# Quadcopter.net
KiCad netlist of a schematic drawn in Altium Designer
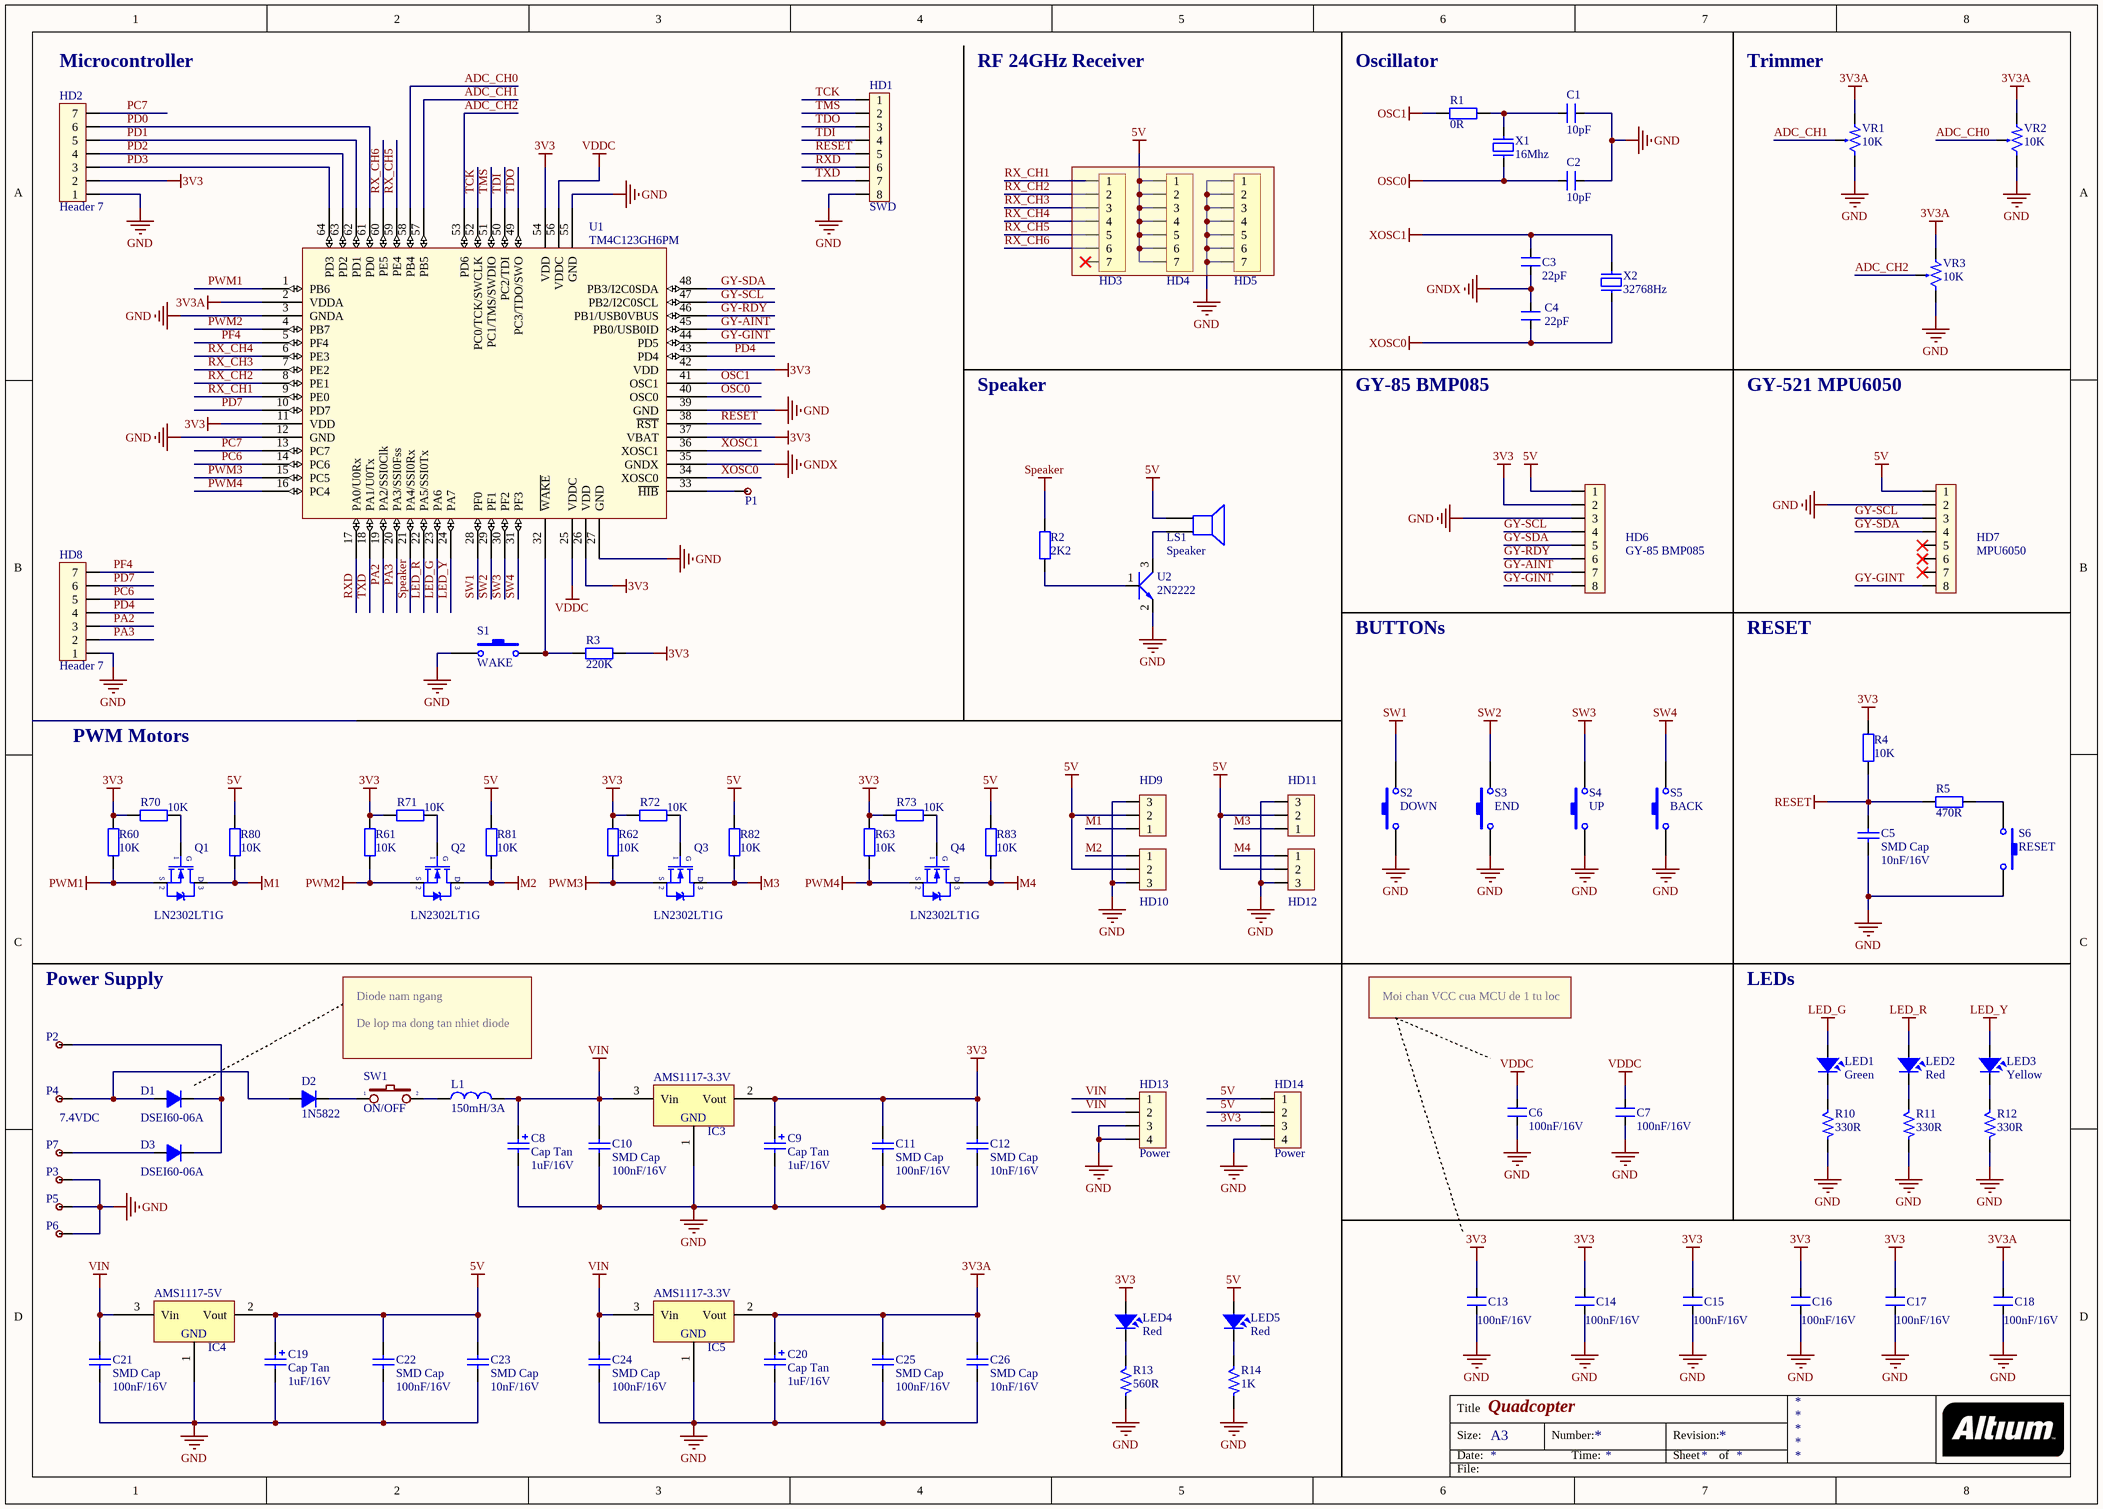
[diagram p0: Quadcopter.SchDoc]

(export (version "E")
  (design (tool "Eeschema 10.0.6"))
  (components
    (comp (ref "C1")
      (value "10pF")
      (footprint "C0603")
      (description "0805-SMD Capacitor")
      (libsource (lib "syhaunguyen") (part "CN1"))
    )
    (comp (ref "C2")
      (value "10pF")
      (footprint "C0603")
      (description "0805-SMD Capacitor")
      (libsource (lib "syhaunguyen") (part "CN1"))
    )
    (comp (ref "C3")
      (value "22pF")
      (footprint "C0603")
      (description "0805-SMD Capacitor")
      (libsource (lib "syhaunguyen") (part "CN1"))
    )
    (comp (ref "C4")
      (value "22pF")
      (footprint "C0603")
      (description "0805-SMD Capacitor")
      (libsource (lib "syhaunguyen") (part "CN1"))
    )
    (comp (ref "C5")
      (value "SMD Cap")
      (footprint "C0603")
      (description "0805-10nF-50V Cap")
      (fields (field (name "ALTIUM_VALUE") "10nF/16V"))
      (libsource (lib "Miscellaneous Devices") (part "Cap"))
    )
    (comp (ref "C6")
      (value "100nF/16V")
      (footprint "C0603")
      (description "0805-SMD Capacitor")
      (fields (field (name "Comment") "SMD Cap"))
      (libsource (lib "syhaunguyen") (part "CN1"))
    )
    (comp (ref "C7")
      (value "100nF/16V")
      (footprint "C0603")
      (description "0805-SMD Capacitor")
      (fields (field (name "Comment") "SMD Cap"))
      (libsource (lib "syhaunguyen") (part "CN1"))
    )
    (comp (ref "C8")
      (value "Cap Tan")
      (footprint "CAP_TANTA_1uF_16V")
      (description "Cap Tantalum")
      (fields (field (name "ALTIUM_VALUE") "1uF/16V"))
      (libsource (lib "PassiveComponents_Sau") (part "Cap Pol2"))
    )
    (comp (ref "C9")
      (value "Cap Tan")
      (footprint "CAP_TANTA_1uF_16V")
      (description "Cap Tantalum")
      (fields (field (name "ALTIUM_VALUE") "1uF/16V"))
      (libsource (lib "PassiveComponents_Sau") (part "Cap Pol2"))
    )
    (comp (ref "C10")
      (value "SMD Cap")
      (footprint "C0603")
      (description "SMD Capacitor")
      (fields (field (name "ALTIUM_VALUE") "100nF/16V"))
      (libsource (lib "PassiveComponents_Sau") (part "Cap Cera"))
    )
    (comp (ref "C11")
      (value "SMD Cap")
      (footprint "C0603")
      (description "SMD Capacitor")
      (fields (field (name "ALTIUM_VALUE") "100nF/16V"))
      (libsource (lib "PassiveComponents_Sau") (part "Cap Cera"))
    )
    (comp (ref "C12")
      (value "SMD Cap")
      (footprint "C0603")
      (description "SMD Capacitor")
      (fields (field (name "ALTIUM_VALUE") "10nF/16V"))
      (libsource (lib "PassiveComponents_Sau") (part "Cap Cera"))
    )
    (comp (ref "C13")
      (value "100nF/16V")
      (footprint "C0603")
      (description "0805-SMD Capacitor")
      (fields (field (name "Comment") "SMD Cap"))
      (libsource (lib "syhaunguyen") (part "CN1"))
    )
    (comp (ref "C14")
      (value "100nF/16V")
      (footprint "C0603")
      (description "0805-SMD Capacitor")
      (fields (field (name "Comment") "SMD Cap"))
      (libsource (lib "syhaunguyen") (part "CN1"))
    )
    (comp (ref "C15")
      (value "100nF/16V")
      (footprint "C0603")
      (description "0805-SMD Capacitor")
      (fields (field (name "Comment") "SMD Cap"))
      (libsource (lib "syhaunguyen") (part "CN1"))
    )
    (comp (ref "C16")
      (value "100nF/16V")
      (footprint "C0603")
      (description "0805-SMD Capacitor")
      (fields (field (name "Comment") "SMD Cap"))
      (libsource (lib "syhaunguyen") (part "CN1"))
    )
    (comp (ref "C17")
      (value "100nF/16V")
      (footprint "C0603")
      (description "0805-SMD Capacitor")
      (fields (field (name "Comment") "SMD Cap"))
      (libsource (lib "syhaunguyen") (part "CN1"))
    )
    (comp (ref "C18")
      (value "100nF/16V")
      (footprint "C0603")
      (description "0805-SMD Capacitor")
      (fields (field (name "Comment") "SMD Cap"))
      (libsource (lib "syhaunguyen") (part "CN1"))
    )
    (comp (ref "C19")
      (value "Cap Tan")
      (footprint "CAP_TANTA_1uF_16V")
      (description "Cap Tantalum")
      (fields (field (name "ALTIUM_VALUE") "1uF/16V"))
      (libsource (lib "PassiveComponents_Sau") (part "Cap Pol2"))
    )
    (comp (ref "C20")
      (value "Cap Tan")
      (footprint "CAP_TANTA_1uF_16V")
      (description "Cap Tantalum")
      (fields (field (name "ALTIUM_VALUE") "1uF/16V"))
      (libsource (lib "PassiveComponents_Sau") (part "Cap Pol2"))
    )
    (comp (ref "C21")
      (value "SMD Cap")
      (footprint "C0603")
      (description "SMD Capacitor")
      (fields (field (name "ALTIUM_VALUE") "100nF/16V"))
      (libsource (lib "PassiveComponents_Sau") (part "Cap Cera"))
    )
    (comp (ref "C22")
      (value "SMD Cap")
      (footprint "C0603")
      (description "SMD Capacitor")
      (fields (field (name "ALTIUM_VALUE") "100nF/16V"))
      (libsource (lib "PassiveComponents_Sau") (part "Cap Cera"))
    )
    (comp (ref "C23")
      (value "SMD Cap")
      (footprint "C0603")
      (description "SMD Capacitor")
      (fields (field (name "ALTIUM_VALUE") "10nF/16V"))
      (libsource (lib "PassiveComponents_Sau") (part "Cap Cera"))
    )
    (comp (ref "C24")
      (value "SMD Cap")
      (footprint "C0603")
      (description "SMD Capacitor")
      (fields (field (name "ALTIUM_VALUE") "100nF/16V"))
      (libsource (lib "PassiveComponents_Sau") (part "Cap Cera"))
    )
    (comp (ref "C25")
      (value "SMD Cap")
      (footprint "C0603")
      (description "SMD Capacitor")
      (fields (field (name "ALTIUM_VALUE") "100nF/16V"))
      (libsource (lib "PassiveComponents_Sau") (part "Cap Cera"))
    )
    (comp (ref "C26")
      (value "SMD Cap")
      (footprint "C0603")
      (description "SMD Capacitor")
      (fields (field (name "ALTIUM_VALUE") "10nF/16V"))
      (libsource (lib "PassiveComponents_Sau") (part "Cap Cera"))
    )
    (comp (ref "D1")
      (value "DSEI60-06A")
      (footprint "DSEI60-06A")
      (description "Diode 60A")
      (libsource (lib "VNELEK") (part "D1A"))
    )
    (comp (ref "D2")
      (value "1N5822")
      (footprint "1N5822")
      (description "Diode  3A")
      (libsource (lib "VNELEK") (part "D1A"))
    )
    (comp (ref "D3")
      (value "DSEI60-06A")
      (footprint "DSEI60-06A")
      (description "Diode 60A")
      (libsource (lib "VNELEK") (part "D1A"))
    )
    (comp (ref "HD1")
      (value "SWD")
      (footprint "Header_8")
      (description "Hedear 8")
      (fields (field (name "CREAT BY") "VanDungEvn@Gmail.com"))
      (libsource (lib "VNELEK") (part "Hed8"))
    )
    (comp (ref "HD2") (value "Header 7") (footprint "Header_7") (libsource (lib "") (part "Hed7_1")))
    (comp (ref "HD3") (value "Header 7") (footprint "Header_7") (libsource (lib "Tran Tuan") (part "Hed7")))
    (comp (ref "HD4") (value "Header 7") (footprint "Header_7") (libsource (lib "Tran Tuan") (part "Hed7")))
    (comp (ref "HD5") (value "Header 7") (footprint "Header_7") (libsource (lib "Tran Tuan") (part "Hed7")))
    (comp (ref "HD6")
      (value "GY-85 BMP085")
      (footprint "Header_8")
      (description "Hedear 8")
      (fields (field (name "CREAT BY") "VanDungEvn@Gmail.com"))
      (libsource (lib "VNELEK") (part "Hed8"))
    )
    (comp (ref "HD7")
      (value "MPU6050")
      (footprint "Header_8")
      (description "Hedear 8")
      (fields (field (name "CREAT BY") "VanDungEvn@Gmail.com"))
      (libsource (lib "VNELEK") (part "Hed8"))
    )
    (comp (ref "HD8") (value "Header 7") (footprint "Header_7") (libsource (lib "") (part "Hed7_1")))
    (comp (ref "HD9")
      (value "Header 3")
      (footprint "JP3H")
      (description "Header 3 (Green)")
      (libsource (lib "") (part "Hed3_1"))
    )
    (comp (ref "HD10")
      (value "Header 3")
      (footprint "JP3H")
      (description "Header 3 (Green)")
      (libsource (lib "VNELEK") (part "Hed3"))
    )
    (comp (ref "HD11")
      (value "Header 3")
      (footprint "JP3H")
      (description "Header 3 (Green)")
      (libsource (lib "") (part "Hed3_1"))
    )
    (comp (ref "HD12")
      (value "Header 3")
      (footprint "JP3H")
      (description "Header 3 (Green)")
      (libsource (lib "VNELEK") (part "Hed3"))
    )
    (comp (ref "HD13")
      (value "Power")
      (footprint "Header_4")
      (description "Header 4 (Green)")
      (libsource (lib "VNELEK") (part "Hed4"))
    )
    (comp (ref "HD14")
      (value "Power")
      (footprint "Header_4")
      (description "Header 4 (Green)")
      (libsource (lib "VNELEK") (part "Hed4"))
    )
    (comp (ref "IC3")
      (value "AMS1117-3.3V")
      (footprint "AMS1117-3.3V")
      (libsource (lib "LuanVanPIR") (part "AMS1117"))
    )
    (comp (ref "IC4")
      (value "AMS1117-5V")
      (footprint "AMS1117-3.3V")
      (libsource (lib "LuanVanPIR") (part "AMS1117"))
    )
    (comp (ref "IC5")
      (value "AMS1117-3.3V")
      (footprint "AMS1117-3.3V")
      (libsource (lib "LuanVanPIR") (part "AMS1117"))
    )
    (comp (ref "L1")
      (value "150mH/3A")
      (footprint "Inductor 150mH,3A")
      (description "Inductor")
      (libsource (lib "VNELEK") (part "L1"))
    )
    (comp (ref "LED1")
      (value "Green")
      (footprint "Led 0805G")
      (description "LED Single colour Green and Red")
      (libsource (lib "VNELEK") (part "LED"))
    )
    (comp (ref "LED2")
      (value "Red")
      (footprint "Led 0805R")
      (description "LED Single colour Green and Red")
      (libsource (lib "VNELEK") (part "LED"))
    )
    (comp (ref "LED3")
      (value "Yellow")
      (footprint "Led 0805Y")
      (description "LED Single colour Green and Red")
      (libsource (lib "VNELEK") (part "LED"))
    )
    (comp (ref "LED4")
      (value "Red")
      (footprint "Led 0805R")
      (description "LED Single colour Green and Red")
      (libsource (lib "VNELEK") (part "LED"))
    )
    (comp (ref "LED5")
      (value "Red")
      (footprint "Led 0805R")
      (description "LED Single colour Green and Red")
      (libsource (lib "VNELEK") (part "LED"))
    )
    (comp (ref "LS1")
      (value "Speaker")
      (footprint "SPEAKER")
      (description "Loudspeaker")
      (fields (field (name "PUBLISHER") "Altium Limited"))
      (libsource (lib "Miscellaneous Devices") (part "Speaker"))
    )
    (comp (ref "P1") (value "Pad") (footprint "TP1") (libsource (lib "Tran Tuan") (part "Pad")))
    (comp (ref "P2") (value "Pad") (footprint "TP1") (libsource (lib "Tran Tuan") (part "Pad")))
    (comp (ref "P3") (value "Pad") (footprint "TP1") (libsource (lib "Tran Tuan") (part "Pad")))
    (comp (ref "P4") (value "Pad") (footprint "TP1") (libsource (lib "Tran Tuan") (part "Pad")))
    (comp (ref "P5") (value "Pad") (footprint "TP1") (libsource (lib "Tran Tuan") (part "Pad")))
    (comp (ref "P6") (value "Pad") (footprint "TP1") (libsource (lib "Tran Tuan") (part "Pad")))
    (comp (ref "P7") (value "Pad") (footprint "TP1") (libsource (lib "Tran Tuan") (part "Pad")))
    (comp (ref "Q1")
      (value "LN2302LT1G")
      (description "20V N-Channel Enhancement-Mode MOSFET")
      (libsource (lib "Tran Tuan") (part "LN2302LT1G"))
    )
    (comp (ref "Q2")
      (value "LN2302LT1G")
      (description "20V N-Channel Enhancement-Mode MOSFET")
      (libsource (lib "Tran Tuan") (part "LN2302LT1G"))
    )
    (comp (ref "Q3")
      (value "LN2302LT1G")
      (description "20V N-Channel Enhancement-Mode MOSFET")
      (libsource (lib "Tran Tuan") (part "LN2302LT1G"))
    )
    (comp (ref "Q4")
      (value "LN2302LT1G")
      (description "20V N-Channel Enhancement-Mode MOSFET")
      (libsource (lib "Tran Tuan") (part "LN2302LT1G"))
    )
    (comp (ref "R1")
      (value "0R")
      (footprint "RESC2012L")
      (description "Resistor")
      (fields (field (name "Comment") "Res2") (field (name "PUBLISHER") "Altium Limited"))
      (libsource (lib "") (part "Res2_2"))
    )
    (comp (ref "R2")
      (value "2K2")
      (footprint "RESC2012L")
      (description "Resistor")
      (fields (field (name "Comment") "Res2") (field (name "PUBLISHER") "Altium Limited"))
      (libsource (lib "Miscellaneous Devices") (part "Res2"))
    )
    (comp (ref "R3")
      (value "220K")
      (footprint "RESC2012L")
      (description "Resistor")
      (fields (field (name "Comment") "Res2") (field (name "PUBLISHER") "Altium Limited"))
      (libsource (lib "") (part "Res2_1"))
    )
    (comp (ref "R4")
      (value "10K")
      (footprint "RESC2012L")
      (description "Resistor")
      (fields (field (name "Comment") "Res2") (field (name "PUBLISHER") "Altium Limited"))
      (libsource (lib "") (part "Res2_3"))
    )
    (comp (ref "R5")
      (value "470R")
      (footprint "RESC2012L")
      (description "Resistor")
      (fields (field (name "Comment") "Res2") (field (name "PUBLISHER") "Altium Limited"))
      (libsource (lib "") (part "Res2_1"))
    )
    (comp (ref "R10")
      (value "330R")
      (footprint "RESC2012L")
      (description "Resistor 1/4W")
      (libsource (lib "VNELEK") (part "R"))
    )
    (comp (ref "R11")
      (value "330R")
      (footprint "RESC2012L")
      (description "Resistor 1/4W")
      (libsource (lib "VNELEK") (part "R"))
    )
    (comp (ref "R12")
      (value "330R")
      (footprint "RESC2012L")
      (description "Resistor 1/4W")
      (libsource (lib "VNELEK") (part "R"))
    )
    (comp (ref "R13")
      (value "560R")
      (footprint "RESC2012L")
      (description "Resistor 1/4W")
      (libsource (lib "VNELEK") (part "R"))
    )
    (comp (ref "R14")
      (value "1K")
      (footprint "RESC2012L")
      (description "Resistor 1/4W")
      (libsource (lib "VNELEK") (part "R"))
    )
    (comp (ref "R60")
      (value "10K")
      (footprint "RESC2012L")
      (description "Resistor")
      (fields (field (name "Comment") "Res2") (field (name "PUBLISHER") "Altium Limited"))
      (libsource (lib "") (part "Res2_3"))
    )
    (comp (ref "R61")
      (value "10K")
      (footprint "RESC2012L")
      (description "Resistor")
      (fields (field (name "Comment") "Res2") (field (name "PUBLISHER") "Altium Limited"))
      (libsource (lib "") (part "Res2_3"))
    )
    (comp (ref "R62")
      (value "10K")
      (footprint "RESC2012L")
      (description "Resistor")
      (fields (field (name "Comment") "Res2") (field (name "PUBLISHER") "Altium Limited"))
      (libsource (lib "") (part "Res2_3"))
    )
    (comp (ref "R63")
      (value "10K")
      (footprint "RESC2012L")
      (description "Resistor")
      (fields (field (name "Comment") "Res2") (field (name "PUBLISHER") "Altium Limited"))
      (libsource (lib "") (part "Res2_3"))
    )
    (comp (ref "R70")
      (value "10K")
      (footprint "RESC2012L")
      (description "Resistor")
      (fields (field (name "Comment") "Res2") (field (name "PUBLISHER") "Altium Limited"))
      (libsource (lib "") (part "Res2_1"))
    )
    (comp (ref "R71")
      (value "10K")
      (footprint "RESC2012L")
      (description "Resistor")
      (fields (field (name "Comment") "Res2") (field (name "PUBLISHER") "Altium Limited"))
      (libsource (lib "") (part "Res2_1"))
    )
    (comp (ref "R72")
      (value "10K")
      (footprint "RESC2012L")
      (description "Resistor")
      (fields (field (name "Comment") "Res2") (field (name "PUBLISHER") "Altium Limited"))
      (libsource (lib "") (part "Res2_1"))
    )
    (comp (ref "R73")
      (value "10K")
      (footprint "RESC2012L")
      (description "Resistor")
      (fields (field (name "Comment") "Res2") (field (name "PUBLISHER") "Altium Limited"))
      (libsource (lib "") (part "Res2_1"))
    )
    (comp (ref "R80")
      (value "10K")
      (footprint "RESC2012L")
      (description "Resistor")
      (fields (field (name "Comment") "Res2") (field (name "PUBLISHER") "Altium Limited"))
      (libsource (lib "") (part "Res2_3"))
    )
    (comp (ref "R81")
      (value "10K")
      (footprint "RESC2012L")
      (description "Resistor")
      (fields (field (name "Comment") "Res2") (field (name "PUBLISHER") "Altium Limited"))
      (libsource (lib "") (part "Res2_3"))
    )
    (comp (ref "R82")
      (value "10K")
      (footprint "RESC2012L")
      (description "Resistor")
      (fields (field (name "Comment") "Res2") (field (name "PUBLISHER") "Altium Limited"))
      (libsource (lib "") (part "Res2_3"))
    )
    (comp (ref "R83")
      (value "10K")
      (footprint "RESC2012L")
      (description "Resistor")
      (fields (field (name "Comment") "Res2") (field (name "PUBLISHER") "Altium Limited"))
      (libsource (lib "") (part "Res2_3"))
    )
    (comp (ref "S1")
      (value "WAKE")
      (footprint "BUTTON 2PIN TRON")
      (description "Switch")
      (fields (field (name "PUBLISHER") "Altium Limited"))
      (libsource (lib "Miscellaneous Devices") (part "SW-PB"))
    )
    (comp (ref "S2")
      (value "DOWN")
      (footprint "BUTTON 2PIN TRON")
      (description "Switch")
      (fields (field (name "PUBLISHER") "Altium Limited"))
      (libsource (lib "Miscellaneous Devices") (part "SW-PB"))
    )
    (comp (ref "S3")
      (value "END")
      (footprint "BUTTON 2PIN TRON")
      (description "Switch")
      (fields (field (name "PUBLISHER") "Altium Limited"))
      (libsource (lib "Miscellaneous Devices") (part "SW-PB"))
    )
    (comp (ref "S4")
      (value "UP")
      (footprint "BUTTON 2PIN TRON")
      (description "Switch")
      (fields (field (name "PUBLISHER") "Altium Limited"))
      (libsource (lib "Miscellaneous Devices") (part "SW-PB"))
    )
    (comp (ref "S5")
      (value "BACK")
      (footprint "BUTTON 2PIN TRON")
      (description "Switch")
      (fields (field (name "PUBLISHER") "Altium Limited"))
      (libsource (lib "Miscellaneous Devices") (part "SW-PB"))
    )
    (comp (ref "S6")
      (value "RESET")
      (footprint "BUTTON 2PIN TRON")
      (description "Switch")
      (fields (field (name "PUBLISHER") "Altium Limited"))
      (libsource (lib "Miscellaneous Devices") (part "SW-PB"))
    )
    (comp (ref "SW1")
      (value "ON/OFF")
      (footprint "CKCD11-101")
      (description "Switch button 2 pin")
      (libsource (lib "VNELEK") (part "SW2"))
    )
    (comp (ref "U1")
      (value "TM4C123GH6PM")
      (footprint "TM4C123GH6PM")
      (description "Tiva C Series Microcontroller")
      (libsource (lib "Tran Tuan") (part "TM4C123GH6PM"))
    )
    (comp (ref "U2")
      (value "2N2222")
      (footprint "MMBT2222A")
      (description "NPN switching transistors")
      (libsource (lib "Tran Tuan") (part "2N2222"))
    )
    (comp (ref "VR1")
      (value "10K")
      (footprint "VR")
      (description "Var Resistor")
      (libsource (lib "VNELEK") (part "VR1"))
    )
    (comp (ref "VR2")
      (value "10K")
      (footprint "VR")
      (description "Var Resistor")
      (libsource (lib "VNELEK") (part "VR1"))
    )
    (comp (ref "VR3")
      (value "10K")
      (footprint "VR")
      (description "Var Resistor")
      (libsource (lib "VNELEK") (part "VR1"))
    )
    (comp (ref "X1")
      (value "16Mhz")
      (footprint "CSTCE16M0V53-R0")
      (description "Crystal For all Crystal 2pin.")
      (libsource (lib "syhaunguyen") (part "XT2"))
    )
    (comp (ref "X2")
      (value "32768Hz")
      (footprint "32.678 Khz")
      (description "Crystal For all Crystal 2pin.")
      (libsource (lib "syhaunguyen") (part "XT2"))
    )
  )
  (nets
    (net (code "1") (name "/ADC_CH0") (class "Default")
      (node (ref "U1") (pin "58") (pinfunction "PB4_58") (pintype "bidirectional"))
      (node (ref "VR2") (pin "2") (pinfunction "2_2") (pintype "passive"))
    )
    (net (code "2") (name "/ADC_CH1") (class "Default")
      (node (ref "U1") (pin "57") (pinfunction "PB5_57") (pintype "bidirectional"))
      (node (ref "VR1") (pin "2") (pinfunction "2_2") (pintype "passive"))
    )
    (net (code "3") (name "/ADC_CH2") (class "Default")
      (node (ref "U1") (pin "53") (pinfunction "PD6_53") (pintype "bidirectional"))
      (node (ref "VR3") (pin "2") (pinfunction "2_2") (pintype "passive"))
    )
    (net (code "4") (name "/GY-AINT") (class "Default")
      (node (ref "HD6") (pin "7") (pinfunction "7_7") (pintype "passive"))
      (node (ref "U1") (pin "45") (pinfunction "PB0/USB0ID_45") (pintype "bidirectional"))
    )
    (net (code "5") (name "/GY-GINT") (class "Default")
      (node (ref "HD6") (pin "8") (pinfunction "8_8") (pintype "passive"))
      (node (ref "HD7") (pin "8") (pinfunction "8_8") (pintype "passive"))
      (node (ref "U1") (pin "44") (pinfunction "PD5_44") (pintype "bidirectional"))
    )
    (net (code "6") (name "/GY-RDY") (class "Default")
      (node (ref "HD6") (pin "6") (pinfunction "6_6") (pintype "passive"))
      (node (ref "U1") (pin "46") (pinfunction "PB1/USB0VBUS_46") (pintype "bidirectional"))
    )
    (net (code "7") (name "/GY-SCL") (class "Default")
      (node (ref "HD6") (pin "4") (pinfunction "4_4") (pintype "passive"))
      (node (ref "HD7") (pin "3") (pinfunction "3_3") (pintype "passive"))
      (node (ref "U1") (pin "47") (pinfunction "PB2/I2C0SCL_47") (pintype "bidirectional"))
    )
    (net (code "8") (name "/GY-SDA") (class "Default")
      (node (ref "HD6") (pin "5") (pinfunction "5_5") (pintype "passive"))
      (node (ref "HD7") (pin "4") (pinfunction "4_4") (pintype "passive"))
      (node (ref "U1") (pin "48") (pinfunction "PB3/I2C0SDA_48") (pintype "bidirectional"))
    )
    (net (code "9") (name "/PA2") (class "Default")
      (node (ref "HD8") (pin "3") (pinfunction "3_3") (pintype "passive"))
      (node (ref "U1") (pin "19") (pinfunction "PA2/SSI0Clk_19") (pintype "bidirectional"))
    )
    (net (code "10") (name "/PA3") (class "Default")
      (node (ref "HD8") (pin "2") (pinfunction "2_2") (pintype "passive"))
      (node (ref "U1") (pin "20") (pinfunction "PA3/SSI0Fss_20") (pintype "bidirectional"))
    )
    (net (code "11") (name "/PC6") (class "Default")
      (node (ref "HD8") (pin "5") (pinfunction "5_5") (pintype "passive"))
      (node (ref "U1") (pin "14") (pinfunction "PC6_14") (pintype "bidirectional"))
    )
    (net (code "12") (name "/PC7") (class "Default")
      (node (ref "HD2") (pin "7") (pinfunction "7_7") (pintype "passive"))
      (node (ref "U1") (pin "13") (pinfunction "PC7_13") (pintype "bidirectional"))
    )
    (net (code "13") (name "/PD0") (class "Default")
      (node (ref "HD2") (pin "6") (pinfunction "6_6") (pintype "passive"))
      (node (ref "U1") (pin "61") (pinfunction "PD0_61") (pintype "bidirectional"))
    )
    (net (code "14") (name "/PD1") (class "Default")
      (node (ref "HD2") (pin "5") (pinfunction "5_5") (pintype "passive"))
      (node (ref "U1") (pin "62") (pinfunction "PD1_62") (pintype "bidirectional"))
    )
    (net (code "15") (name "/PD2") (class "Default")
      (node (ref "HD2") (pin "4") (pinfunction "4_4") (pintype "passive"))
      (node (ref "U1") (pin "63") (pinfunction "PD2_63") (pintype "bidirectional"))
    )
    (net (code "16") (name "/PD3") (class "Default")
      (node (ref "HD2") (pin "3") (pinfunction "3_3") (pintype "passive"))
      (node (ref "U1") (pin "64") (pinfunction "PD3_64") (pintype "bidirectional"))
    )
    (net (code "17") (name "/PD4") (class "Default")
      (node (ref "HD8") (pin "4") (pinfunction "4_4") (pintype "passive"))
      (node (ref "U1") (pin "43") (pinfunction "PD4_43") (pintype "bidirectional"))
    )
    (net (code "18") (name "/PD7") (class "Default")
      (node (ref "HD8") (pin "6") (pinfunction "6_6") (pintype "passive"))
      (node (ref "U1") (pin "10") (pinfunction "PD7_10") (pintype "bidirectional"))
    )
    (net (code "19") (name "/PF4") (class "Default")
      (node (ref "HD8") (pin "7") (pinfunction "7_7") (pintype "passive"))
      (node (ref "U1") (pin "5") (pinfunction "PF4_5") (pintype "bidirectional"))
    )
    (net (code "20") (name "/RXD") (class "Default")
      (node (ref "HD1") (pin "6") (pinfunction "6_6") (pintype "passive"))
      (node (ref "U1") (pin "17") (pinfunction "PA0/U0Rx_17") (pintype "bidirectional"))
    )
    (net (code "21") (name "/RX_CH1") (class "Default")
      (node (ref "HD3") (pin "1") (pinfunction "1_1") (pintype "passive"))
      (node (ref "U1") (pin "9") (pinfunction "PE0_9") (pintype "bidirectional"))
    )
    (net (code "22") (name "/RX_CH2") (class "Default")
      (node (ref "HD3") (pin "2") (pinfunction "2_2") (pintype "passive"))
      (node (ref "U1") (pin "8") (pinfunction "PE1_8") (pintype "bidirectional"))
    )
    (net (code "23") (name "/RX_CH3") (class "Default")
      (node (ref "HD3") (pin "3") (pinfunction "3_3") (pintype "passive"))
      (node (ref "U1") (pin "7") (pinfunction "PE2_7") (pintype "bidirectional"))
    )
    (net (code "24") (name "/RX_CH4") (class "Default")
      (node (ref "HD3") (pin "4") (pinfunction "4_4") (pintype "passive"))
      (node (ref "U1") (pin "6") (pinfunction "PE3_6") (pintype "bidirectional"))
    )
    (net (code "25") (name "/RX_CH5") (class "Default")
      (node (ref "HD3") (pin "5") (pinfunction "5_5") (pintype "passive"))
      (node (ref "U1") (pin "59") (pinfunction "PE4_59") (pintype "bidirectional"))
    )
    (net (code "26") (name "/RX_CH6") (class "Default")
      (node (ref "HD3") (pin "6") (pinfunction "6_6") (pintype "passive"))
      (node (ref "U1") (pin "60") (pinfunction "PE5_60") (pintype "bidirectional"))
    )
    (net (code "27") (name "/TCK") (class "Default")
      (node (ref "HD1") (pin "1") (pinfunction "1_1") (pintype "passive"))
      (node (ref "U1") (pin "52") (pinfunction "PC0/TCK/SWCLK_52") (pintype "bidirectional"))
    )
    (net (code "28") (name "/TDI") (class "Default")
      (node (ref "HD1") (pin "4") (pinfunction "4_4") (pintype "passive"))
      (node (ref "U1") (pin "50") (pinfunction "PC2/TDI_50") (pintype "bidirectional"))
    )
    (net (code "29") (name "/TDO") (class "Default")
      (node (ref "HD1") (pin "3") (pinfunction "3_3") (pintype "passive"))
      (node (ref "U1") (pin "49") (pinfunction "PC3/TDO/SWO_49") (pintype "bidirectional"))
    )
    (net (code "30") (name "/TMS") (class "Default")
      (node (ref "HD1") (pin "2") (pinfunction "2_2") (pintype "passive"))
      (node (ref "U1") (pin "51") (pinfunction "PC1/TMS/SWDIO_51") (pintype "bidirectional"))
    )
    (net (code "31") (name "/TXD") (class "Default")
      (node (ref "HD1") (pin "7") (pinfunction "7_7") (pintype "passive"))
      (node (ref "U1") (pin "18") (pinfunction "PA1/U0Tx_18") (pintype "bidirectional"))
    )
    (net (code "32") (name "3V3") (class "Default")
      (node (ref "C11") (pin "2") (pinfunction "2_2") (pintype "passive"))
      (node (ref "C12") (pin "2") (pinfunction "2_2") (pintype "passive"))
      (node (ref "C13") (pin "1") (pinfunction "1_1") (pintype "passive"))
      (node (ref "C14") (pin "1") (pinfunction "1_1") (pintype "passive"))
      (node (ref "C15") (pin "1") (pinfunction "1_1") (pintype "passive"))
      (node (ref "C16") (pin "1") (pinfunction "1_1") (pintype "passive"))
      (node (ref "C17") (pin "1") (pinfunction "1_1") (pintype "passive"))
      (node (ref "C9") (pin "1") (pinfunction "+_1") (pintype "passive"))
      (node (ref "HD14") (pin "3") (pinfunction "3_3") (pintype "passive"))
      (node (ref "HD2") (pin "2") (pinfunction "2_2") (pintype "passive"))
      (node (ref "HD6") (pin "2") (pinfunction "2_2") (pintype "passive"))
      (node (ref "IC3") (pin "2") (pinfunction "Vout_2") (pintype "passive"))
      (node (ref "LED4") (pin "1") (pinfunction "1_1") (pintype "passive"))
      (node (ref "R3") (pin "1") (pinfunction "1_1") (pintype "passive"))
      (node (ref "R4") (pin "2") (pinfunction "2_2") (pintype "passive"))
      (node (ref "R60") (pin "2") (pinfunction "2_2") (pintype "passive"))
      (node (ref "R61") (pin "2") (pinfunction "2_2") (pintype "passive"))
      (node (ref "R62") (pin "2") (pinfunction "2_2") (pintype "passive"))
      (node (ref "R63") (pin "2") (pinfunction "2_2") (pintype "passive"))
      (node (ref "R70") (pin "2") (pinfunction "2_2") (pintype "passive"))
      (node (ref "R71") (pin "2") (pinfunction "2_2") (pintype "passive"))
      (node (ref "R72") (pin "2") (pinfunction "2_2") (pintype "passive"))
      (node (ref "R73") (pin "2") (pinfunction "2_2") (pintype "passive"))
      (node (ref "U1") (pin "11") (pinfunction "VDD_11") (pintype "power_in"))
      (node (ref "U1") (pin "26") (pinfunction "VDD_26") (pintype "power_in"))
      (node (ref "U1") (pin "37") (pinfunction "VBAT_37") (pintype "power_in"))
      (node (ref "U1") (pin "42") (pinfunction "VDD_42") (pintype "power_in"))
      (node (ref "U1") (pin "54") (pinfunction "VDD_54") (pintype "power_in"))
    )
    (net (code "33") (name "3V3A") (class "Default")
      (node (ref "C18") (pin "1") (pinfunction "1_1") (pintype "passive"))
      (node (ref "C20") (pin "1") (pinfunction "+_1") (pintype "passive"))
      (node (ref "C25") (pin "2") (pinfunction "2_2") (pintype "passive"))
      (node (ref "C26") (pin "2") (pinfunction "2_2") (pintype "passive"))
      (node (ref "IC5") (pin "2") (pinfunction "Vout_2") (pintype "passive"))
      (node (ref "U1") (pin "2") (pinfunction "VDDA_2") (pintype "power_in"))
      (node (ref "VR1") (pin "1") (pinfunction "1_1") (pintype "passive"))
      (node (ref "VR2") (pin "1") (pinfunction "1_1") (pintype "passive"))
      (node (ref "VR3") (pin "1") (pinfunction "1_1") (pintype "passive"))
    )
    (net (code "34") (name "5V") (class "Default")
      (node (ref "C19") (pin "1") (pinfunction "+_1") (pintype "passive"))
      (node (ref "C22") (pin "2") (pinfunction "2_2") (pintype "passive"))
      (node (ref "C23") (pin "2") (pinfunction "2_2") (pintype "passive"))
      (node (ref "HD10") (pin "2") (pinfunction "2_2") (pintype "passive"))
      (node (ref "HD11") (pin "2") (pinfunction "2_2") (pintype "passive"))
      (node (ref "HD12") (pin "2") (pinfunction "2_2") (pintype "passive"))
      (node (ref "HD14") (pin "1") (pinfunction "1_1") (pintype "passive"))
      (node (ref "HD14") (pin "2") (pinfunction "2_2") (pintype "passive"))
      (node (ref "HD4") (pin "1") (pinfunction "1_1") (pintype "passive"))
      (node (ref "HD4") (pin "2") (pinfunction "2_2") (pintype "passive"))
      (node (ref "HD4") (pin "3") (pinfunction "3_3") (pintype "passive"))
      (node (ref "HD4") (pin "4") (pinfunction "4_4") (pintype "passive"))
      (node (ref "HD4") (pin "5") (pinfunction "5_5") (pintype "passive"))
      (node (ref "HD4") (pin "6") (pinfunction "6_6") (pintype "passive"))
      (node (ref "HD4") (pin "7") (pinfunction "7_7") (pintype "passive"))
      (node (ref "HD6") (pin "1") (pinfunction "1_1") (pintype "passive"))
      (node (ref "HD7") (pin "1") (pinfunction "1_1") (pintype "passive"))
      (node (ref "HD9") (pin "2") (pinfunction "2_2") (pintype "passive"))
      (node (ref "IC4") (pin "2") (pinfunction "Vout_2") (pintype "passive"))
      (node (ref "LED5") (pin "1") (pinfunction "1_1") (pintype "passive"))
      (node (ref "LS1") (pin "2") (pinfunction "2_2") (pintype "passive"))
      (node (ref "R80") (pin "2") (pinfunction "2_2") (pintype "passive"))
      (node (ref "R81") (pin "2") (pinfunction "2_2") (pintype "passive"))
      (node (ref "R82") (pin "2") (pinfunction "2_2") (pintype "passive"))
      (node (ref "R83") (pin "2") (pinfunction "2_2") (pintype "passive"))
    )
    (net (code "35") (name "GND") (class "Default")
      (node (ref "C1") (pin "1") (pinfunction "1_1") (pintype "passive"))
      (node (ref "C10") (pin "1") (pinfunction "1_1") (pintype "passive"))
      (node (ref "C11") (pin "1") (pinfunction "1_1") (pintype "passive"))
      (node (ref "C12") (pin "1") (pinfunction "1_1") (pintype "passive"))
      (node (ref "C13") (pin "2") (pinfunction "2_2") (pintype "passive"))
      (node (ref "C14") (pin "2") (pinfunction "2_2") (pintype "passive"))
      (node (ref "C15") (pin "2") (pinfunction "2_2") (pintype "passive"))
      (node (ref "C16") (pin "2") (pinfunction "2_2") (pintype "passive"))
      (node (ref "C17") (pin "2") (pinfunction "2_2") (pintype "passive"))
      (node (ref "C18") (pin "2") (pinfunction "2_2") (pintype "passive"))
      (node (ref "C19") (pin "2") (pinfunction "-_2") (pintype "passive"))
      (node (ref "C2") (pin "1") (pinfunction "1_1") (pintype "passive"))
      (node (ref "C20") (pin "2") (pinfunction "-_2") (pintype "passive"))
      (node (ref "C21") (pin "1") (pinfunction "1_1") (pintype "passive"))
      (node (ref "C22") (pin "1") (pinfunction "1_1") (pintype "passive"))
      (node (ref "C23") (pin "1") (pinfunction "1_1") (pintype "passive"))
      (node (ref "C24") (pin "1") (pinfunction "1_1") (pintype "passive"))
      (node (ref "C25") (pin "1") (pinfunction "1_1") (pintype "passive"))
      (node (ref "C26") (pin "1") (pinfunction "1_1") (pintype "passive"))
      (node (ref "C5") (pin "2") (pinfunction "2_2") (pintype "passive"))
      (node (ref "C6") (pin "2") (pinfunction "2_2") (pintype "passive"))
      (node (ref "C7") (pin "2") (pinfunction "2_2") (pintype "passive"))
      (node (ref "C8") (pin "2") (pinfunction "-_2") (pintype "passive"))
      (node (ref "C9") (pin "2") (pinfunction "-_2") (pintype "passive"))
      (node (ref "HD1") (pin "8") (pinfunction "8_8") (pintype "passive"))
      (node (ref "HD10") (pin "3") (pinfunction "3_3") (pintype "passive"))
      (node (ref "HD11") (pin "3") (pinfunction "3_3") (pintype "passive"))
      (node (ref "HD12") (pin "3") (pinfunction "3_3") (pintype "passive"))
      (node (ref "HD13") (pin "3") (pinfunction "3_3") (pintype "passive"))
      (node (ref "HD13") (pin "4") (pinfunction "4_4") (pintype "passive"))
      (node (ref "HD14") (pin "4") (pinfunction "4_4") (pintype "passive"))
      (node (ref "HD2") (pin "1") (pinfunction "1_1") (pintype "passive"))
      (node (ref "HD5") (pin "1") (pinfunction "1_1") (pintype "passive"))
      (node (ref "HD5") (pin "2") (pinfunction "2_2") (pintype "passive"))
      (node (ref "HD5") (pin "3") (pinfunction "3_3") (pintype "passive"))
      (node (ref "HD5") (pin "4") (pinfunction "4_4") (pintype "passive"))
      (node (ref "HD5") (pin "5") (pinfunction "5_5") (pintype "passive"))
      (node (ref "HD5") (pin "6") (pinfunction "6_6") (pintype "passive"))
      (node (ref "HD5") (pin "7") (pinfunction "7_7") (pintype "passive"))
      (node (ref "HD6") (pin "3") (pinfunction "3_3") (pintype "passive"))
      (node (ref "HD7") (pin "2") (pinfunction "2_2") (pintype "passive"))
      (node (ref "HD8") (pin "1") (pinfunction "1_1") (pintype "passive"))
      (node (ref "HD9") (pin "3") (pinfunction "3_3") (pintype "passive"))
      (node (ref "IC3") (pin "1") (pinfunction "GND_1") (pintype "passive"))
      (node (ref "IC4") (pin "1") (pinfunction "GND_1") (pintype "passive"))
      (node (ref "IC5") (pin "1") (pinfunction "GND_1") (pintype "passive"))
      (node (ref "P3") (pin "1") (pinfunction "1_1") (pintype "passive"))
      (node (ref "P5") (pin "1") (pinfunction "1_1") (pintype "passive"))
      (node (ref "P6") (pin "1") (pinfunction "1_1") (pintype "passive"))
      (node (ref "R10") (pin "2") (pinfunction "2_2") (pintype "passive"))
      (node (ref "R11") (pin "2") (pinfunction "2_2") (pintype "passive"))
      (node (ref "R12") (pin "2") (pinfunction "2_2") (pintype "passive"))
      (node (ref "R13") (pin "2") (pinfunction "2_2") (pintype "passive"))
      (node (ref "R14") (pin "2") (pinfunction "2_2") (pintype "passive"))
      (node (ref "S1") (pin "1") (pinfunction "1_1") (pintype "passive"))
      (node (ref "S2") (pin "1") (pinfunction "1_1") (pintype "passive"))
      (node (ref "S3") (pin "1") (pinfunction "1_1") (pintype "passive"))
      (node (ref "S4") (pin "1") (pinfunction "1_1") (pintype "passive"))
      (node (ref "S5") (pin "1") (pinfunction "1_1") (pintype "passive"))
      (node (ref "S6") (pin "2") (pinfunction "2_2") (pintype "passive"))
      (node (ref "U1") (pin "12") (pinfunction "GND_12") (pintype "power_in"))
      (node (ref "U1") (pin "27") (pinfunction "GND_27") (pintype "power_in"))
      (node (ref "U1") (pin "3") (pinfunction "GNDA_3") (pintype "power_in"))
      (node (ref "U1") (pin "39") (pinfunction "GND_39") (pintype "power_in"))
      (node (ref "U1") (pin "55") (pinfunction "GND_55") (pintype "power_in"))
      (node (ref "U2") (pin "2") (pinfunction "E_2") (pintype "passive"))
      (node (ref "VR1") (pin "3") (pinfunction "3_3") (pintype "passive"))
      (node (ref "VR2") (pin "3") (pinfunction "3_3") (pintype "passive"))
      (node (ref "VR3") (pin "3") (pinfunction "3_3") (pintype "passive"))
    )
    (net (code "36") (name "GNDX") (class "Default")
      (node (ref "C3") (pin "2") (pinfunction "2_2") (pintype "passive"))
      (node (ref "C4") (pin "1") (pinfunction "1_1") (pintype "passive"))
      (node (ref "U1") (pin "35") (pinfunction "GNDX_35") (pintype "power_in"))
    )
    (net (code "37") (name "LED_G") (class "Default")
      (node (ref "LED1") (pin "1") (pinfunction "1_1") (pintype "passive"))
      (node (ref "U1") (pin "23") (pinfunction "PA6_23") (pintype "bidirectional"))
    )
    (net (code "38") (name "LED_R") (class "Default")
      (node (ref "LED2") (pin "1") (pinfunction "1_1") (pintype "passive"))
      (node (ref "U1") (pin "22") (pinfunction "PA5/SSI0Tx_22") (pintype "bidirectional"))
    )
    (net (code "39") (name "LED_Y") (class "Default")
      (node (ref "LED3") (pin "1") (pinfunction "1_1") (pintype "passive"))
      (node (ref "U1") (pin "24") (pinfunction "PA7_24") (pintype "bidirectional"))
    )
    (net (code "40") (name "M1") (class "Default")
      (node (ref "HD9") (pin "1") (pinfunction "1_1") (pintype "passive"))
      (node (ref "Q1") (pin "3") (pinfunction "D_3") (pintype "passive"))
      (node (ref "R80") (pin "1") (pinfunction "1_1") (pintype "passive"))
    )
    (net (code "41") (name "M2") (class "Default")
      (node (ref "HD10") (pin "1") (pinfunction "1_1") (pintype "passive"))
      (node (ref "Q2") (pin "3") (pinfunction "D_3") (pintype "passive"))
      (node (ref "R81") (pin "1") (pinfunction "1_1") (pintype "passive"))
    )
    (net (code "42") (name "M3") (class "Default")
      (node (ref "HD11") (pin "1") (pinfunction "1_1") (pintype "passive"))
      (node (ref "Q3") (pin "3") (pinfunction "D_3") (pintype "passive"))
      (node (ref "R82") (pin "1") (pinfunction "1_1") (pintype "passive"))
    )
    (net (code "43") (name "M4") (class "Default")
      (node (ref "HD12") (pin "1") (pinfunction "1_1") (pintype "passive"))
      (node (ref "Q4") (pin "3") (pinfunction "D_3") (pintype "passive"))
      (node (ref "R83") (pin "1") (pinfunction "1_1") (pintype "passive"))
    )
    (net (code "44") (name "Net-(C1-Pad2)") (class "Default")
      (node (ref "C1") (pin "2") (pinfunction "2_2") (pintype "passive"))
      (node (ref "R1") (pin "2") (pinfunction "2_2") (pintype "passive"))
      (node (ref "X1") (pin "1") (pinfunction "1_1") (pintype "passive"))
    )
    (net (code "45") (name "Net-(D1-A)") (class "Default")
      (node (ref "D1") (pin "2") (pinfunction "A_2") (pintype "passive"))
      (node (ref "D3") (pin "2") (pinfunction "A_2") (pintype "passive"))
      (node (ref "P2") (pin "1") (pinfunction "1_1") (pintype "passive"))
    )
    (net (code "46") (name "Net-(D1-K)") (class "Default")
      (node (ref "D1") (pin "1") (pinfunction "K_1") (pintype "passive"))
      (node (ref "D2") (pin "1") (pinfunction "K_1") (pintype "passive"))
      (node (ref "P4") (pin "1") (pinfunction "1_1") (pintype "passive"))
    )
    (net (code "47") (name "Net-(D2-A)") (class "Default")
      (node (ref "D2") (pin "2") (pinfunction "A_2") (pintype "passive"))
      (node (ref "SW1") (pin "1") (pinfunction "1_1") (pintype "passive"))
    )
    (net (code "48") (name "Net-(D3-K)") (class "Default")
      (node (ref "D3") (pin "1") (pinfunction "K_1") (pintype "passive"))
      (node (ref "P7") (pin "1") (pinfunction "1_1") (pintype "passive"))
    )
    (net (code "49") (name "Net-(L1-Pad1)") (class "Default")
      (node (ref "L1") (pin "1") (pinfunction "1_1") (pintype "passive"))
      (node (ref "SW1") (pin "2") (pinfunction "2_2") (pintype "passive"))
    )
    (net (code "50") (name "Net-(LED1-Pad2)") (class "Default")
      (node (ref "LED1") (pin "2") (pinfunction "2_2") (pintype "passive"))
      (node (ref "R10") (pin "1") (pinfunction "1_1") (pintype "passive"))
    )
    (net (code "51") (name "Net-(LED2-Pad2)") (class "Default")
      (node (ref "LED2") (pin "2") (pinfunction "2_2") (pintype "passive"))
      (node (ref "R11") (pin "1") (pinfunction "1_1") (pintype "passive"))
    )
    (net (code "52") (name "Net-(LED3-Pad2)") (class "Default")
      (node (ref "LED3") (pin "2") (pinfunction "2_2") (pintype "passive"))
      (node (ref "R12") (pin "1") (pinfunction "1_1") (pintype "passive"))
    )
    (net (code "53") (name "Net-(LED4-Pad2)") (class "Default")
      (node (ref "LED4") (pin "2") (pinfunction "2_2") (pintype "passive"))
      (node (ref "R13") (pin "1") (pinfunction "1_1") (pintype "passive"))
    )
    (net (code "54") (name "Net-(LED5-Pad2)") (class "Default")
      (node (ref "LED5") (pin "2") (pinfunction "2_2") (pintype "passive"))
      (node (ref "R14") (pin "1") (pinfunction "1_1") (pintype "passive"))
    )
    (net (code "55") (name "Net-(Q1-G)") (class "Default")
      (node (ref "Q1") (pin "1") (pinfunction "G_1") (pintype "passive"))
      (node (ref "R70") (pin "1") (pinfunction "1_1") (pintype "passive"))
    )
    (net (code "56") (name "Net-(Q2-G)") (class "Default")
      (node (ref "Q2") (pin "1") (pinfunction "G_1") (pintype "passive"))
      (node (ref "R71") (pin "1") (pinfunction "1_1") (pintype "passive"))
    )
    (net (code "57") (name "Net-(Q3-G)") (class "Default")
      (node (ref "Q3") (pin "1") (pinfunction "G_1") (pintype "passive"))
      (node (ref "R72") (pin "1") (pinfunction "1_1") (pintype "passive"))
    )
    (net (code "58") (name "Net-(Q4-G)") (class "Default")
      (node (ref "Q4") (pin "1") (pinfunction "G_1") (pintype "passive"))
      (node (ref "R73") (pin "1") (pinfunction "1_1") (pintype "passive"))
    )
    (net (code "59") (name "Net-(R5-Pad1)") (class "Default")
      (node (ref "R5") (pin "1") (pinfunction "1_1") (pintype "passive"))
      (node (ref "S6") (pin "1") (pinfunction "1_1") (pintype "passive"))
    )
    (net (code "60") (name "Net-(U1-~{HIB})") (class "Default")
      (node (ref "P1") (pin "1") (pinfunction "1_1") (pintype "passive"))
      (node (ref "U1") (pin "33") (pinfunction "~{HIB}_33") (pintype "passive"))
    )
    (net (code "61") (name "Net-(U1-~{WAKE})") (class "Default")
      (node (ref "R3") (pin "2") (pinfunction "2_2") (pintype "passive"))
      (node (ref "S1") (pin "2") (pinfunction "2_2") (pintype "passive"))
      (node (ref "U1") (pin "32") (pinfunction "~{WAKE}_32") (pintype "passive"))
    )
    (net (code "62") (name "Net-(U2-B)") (class "Default")
      (node (ref "R2") (pin "2") (pinfunction "2_2") (pintype "passive"))
      (node (ref "U2") (pin "1") (pinfunction "B_1") (pintype "passive"))
    )
    (net (code "63") (name "Net-(U2-C)") (class "Default")
      (node (ref "LS1") (pin "1") (pinfunction "1_1") (pintype "passive"))
      (node (ref "U2") (pin "3") (pinfunction "C_3") (pintype "passive"))
    )
    (net (code "64") (name "OSC0") (class "Default")
      (node (ref "C2") (pin "2") (pinfunction "2_2") (pintype "passive"))
      (node (ref "U1") (pin "40") (pinfunction "OSC0_40") (pintype "passive"))
      (node (ref "X1") (pin "2") (pinfunction "2_2") (pintype "passive"))
    )
    (net (code "65") (name "OSC1") (class "Default")
      (node (ref "R1") (pin "1") (pinfunction "1_1") (pintype "passive"))
      (node (ref "U1") (pin "41") (pinfunction "OSC1_41") (pintype "passive"))
    )
    (net (code "66") (name "PWM1") (class "Default")
      (node (ref "Q1") (pin "2") (pinfunction "S_2") (pintype "passive"))
      (node (ref "R60") (pin "1") (pinfunction "1_1") (pintype "passive"))
      (node (ref "U1") (pin "1") (pinfunction "PB6_1") (pintype "bidirectional"))
    )
    (net (code "67") (name "PWM2") (class "Default")
      (node (ref "Q2") (pin "2") (pinfunction "S_2") (pintype "passive"))
      (node (ref "R61") (pin "1") (pinfunction "1_1") (pintype "passive"))
      (node (ref "U1") (pin "4") (pinfunction "PB7_4") (pintype "bidirectional"))
    )
    (net (code "68") (name "PWM3") (class "Default")
      (node (ref "Q3") (pin "2") (pinfunction "S_2") (pintype "passive"))
      (node (ref "R62") (pin "1") (pinfunction "1_1") (pintype "passive"))
      (node (ref "U1") (pin "15") (pinfunction "PC5_15") (pintype "bidirectional"))
    )
    (net (code "69") (name "PWM4") (class "Default")
      (node (ref "Q4") (pin "2") (pinfunction "S_2") (pintype "passive"))
      (node (ref "R63") (pin "1") (pinfunction "1_1") (pintype "passive"))
      (node (ref "U1") (pin "16") (pinfunction "PC4_16") (pintype "bidirectional"))
    )
    (net (code "70") (name "RESET") (class "Default")
      (node (ref "C5") (pin "1") (pinfunction "1_1") (pintype "passive"))
      (node (ref "HD1") (pin "5") (pinfunction "5_5") (pintype "passive"))
      (node (ref "R4") (pin "1") (pinfunction "1_1") (pintype "passive"))
      (node (ref "R5") (pin "2") (pinfunction "2_2") (pintype "passive"))
      (node (ref "U1") (pin "38") (pinfunction "~{RST}_38") (pintype "passive"))
    )
    (net (code "71") (name "SW1") (class "Default")
      (node (ref "S2") (pin "2") (pinfunction "2_2") (pintype "passive"))
      (node (ref "U1") (pin "28") (pinfunction "PF0_28") (pintype "bidirectional"))
    )
    (net (code "72") (name "SW2") (class "Default")
      (node (ref "S3") (pin "2") (pinfunction "2_2") (pintype "passive"))
      (node (ref "U1") (pin "29") (pinfunction "PF1_29") (pintype "bidirectional"))
    )
    (net (code "73") (name "SW3") (class "Default")
      (node (ref "S4") (pin "2") (pinfunction "2_2") (pintype "passive"))
      (node (ref "U1") (pin "30") (pinfunction "PF2_30") (pintype "bidirectional"))
    )
    (net (code "74") (name "SW4") (class "Default")
      (node (ref "S5") (pin "2") (pinfunction "2_2") (pintype "passive"))
      (node (ref "U1") (pin "31") (pinfunction "PF3_31") (pintype "bidirectional"))
    )
    (net (code "75") (name "Speaker") (class "Default")
      (node (ref "R2") (pin "1") (pinfunction "1_1") (pintype "passive"))
      (node (ref "U1") (pin "21") (pinfunction "PA4/SSI0Rx_21") (pintype "bidirectional"))
    )
    (net (code "76") (name "VDDC") (class "Default")
      (node (ref "C6") (pin "1") (pinfunction "1_1") (pintype "passive"))
      (node (ref "C7") (pin "1") (pinfunction "1_1") (pintype "passive"))
      (node (ref "U1") (pin "25") (pinfunction "VDDC_25") (pintype "power_in"))
      (node (ref "U1") (pin "56") (pinfunction "VDDC_56") (pintype "power_in"))
    )
    (net (code "77") (name "VIN") (class "Default")
      (node (ref "C10") (pin "2") (pinfunction "2_2") (pintype "passive"))
      (node (ref "C21") (pin "2") (pinfunction "2_2") (pintype "passive"))
      (node (ref "C24") (pin "2") (pinfunction "2_2") (pintype "passive"))
      (node (ref "C8") (pin "1") (pinfunction "+_1") (pintype "passive"))
      (node (ref "HD13") (pin "1") (pinfunction "1_1") (pintype "passive"))
      (node (ref "HD13") (pin "2") (pinfunction "2_2") (pintype "passive"))
      (node (ref "IC3") (pin "3") (pinfunction "Vin_3") (pintype "passive"))
      (node (ref "IC4") (pin "3") (pinfunction "Vin_3") (pintype "passive"))
      (node (ref "IC5") (pin "3") (pinfunction "Vin_3") (pintype "passive"))
      (node (ref "L1") (pin "2") (pinfunction "2_2") (pintype "passive"))
    )
    (net (code "78") (name "XOSC0") (class "Default")
      (node (ref "C4") (pin "2") (pinfunction "2_2") (pintype "passive"))
      (node (ref "U1") (pin "34") (pinfunction "XOSC0_34") (pintype "passive"))
      (node (ref "X2") (pin "2") (pinfunction "2_2") (pintype "passive"))
    )
    (net (code "79") (name "XOSC1") (class "Default")
      (node (ref "C3") (pin "1") (pinfunction "1_1") (pintype "passive"))
      (node (ref "U1") (pin "36") (pinfunction "XOSC1_36") (pintype "passive"))
      (node (ref "X2") (pin "1") (pinfunction "1_1") (pintype "passive"))
    )
    (net (code "80") (name "unconnected-(HD3-Pad7)") (class "Default")
      (node (ref "HD3") (pin "7") (pinfunction "7_7") (pintype "passive+no_connect"))
    )
    (net (code "81") (name "unconnected-(HD7-Pad5)") (class "Default")
      (node (ref "HD7") (pin "5") (pinfunction "5_5") (pintype "passive+no_connect"))
    )
    (net (code "82") (name "unconnected-(HD7-Pad6)") (class "Default")
      (node (ref "HD7") (pin "6") (pinfunction "6_6") (pintype "passive+no_connect"))
    )
    (net (code "83") (name "unconnected-(HD7-Pad7)") (class "Default")
      (node (ref "HD7") (pin "7") (pinfunction "7_7") (pintype "passive+no_connect"))
    )
  )
)
